# STM32.net
KiCad netlist of a schematic drawn in Altium Designer
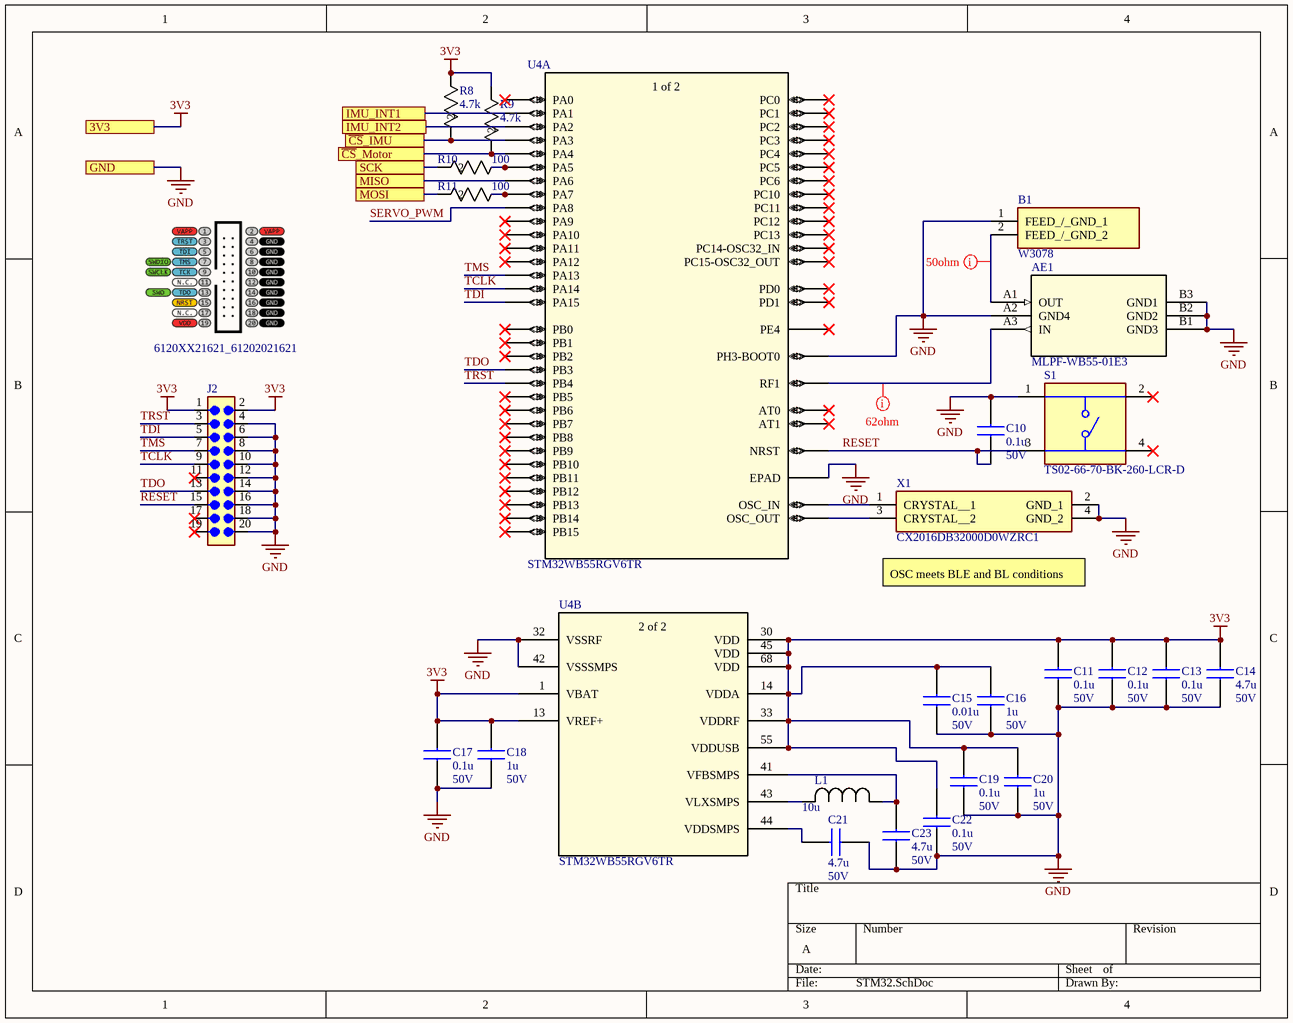
[diagram p0: STM32.SchDoc]

(export (version "E")
  (design (tool "Eeschema 10.0.6"))
  (components
    (comp (ref "AE1")
      (value "MLPF-WB55-01E3")
      (footprint "MLPF-WB55-01E3_STM")
      (description "2.4 GHz Matched filter companion chip for STM32WB55Cx and STM32WB55Rx")
      (fields (field (name "COPYRIGHT") "Copyright (C) 2025 Ultra Librarian. All rights reserved."))
      (libsource (lib "MLPF-WB55-01E3") (part "MLPF-WB55-01E3"))
    )
    (comp (ref "B1")
      (value "W3078")
      (footprint "W3078")
      (description "Antennas CERAMIC W3078 GC380H N")
      (fields (field (name "MOUSER PART NUMBER") "673-W3078"))
      (libsource (lib "W3078") (part "W3078"))
    )
    (comp (ref "C10")
      (value "0.1u")
      (footprint "CAPC2012X145N")
      (description "Multilayer Ceramic Chip Capacitors, Capacitance=0.1u")
      (fields
        (field (name "MANUFACTURER_PART_NUMBER") "KAM21BR71H104JM")
        (field (name "RATED VOLTAGE") "50V")
      )
      (libsource (lib "Caps") (part "KAM21BR71H104JM"))
    )
    (comp (ref "C11")
      (value "0.1u")
      (footprint "CAPC2012X145N")
      (description "Multilayer Ceramic Chip Capacitors, Capacitance=0.1u")
      (fields
        (field (name "MANUFACTURER_PART_NUMBER") "KAM21BR71H104JM")
        (field (name "RATED VOLTAGE") "50V")
      )
      (libsource (lib "Caps") (part "KAM21BR71H104JM"))
    )
    (comp (ref "C12")
      (value "0.1u")
      (footprint "CAPC2012X145N")
      (description "Multilayer Ceramic Chip Capacitors, Capacitance=0.1u")
      (fields
        (field (name "MANUFACTURER_PART_NUMBER") "KAM21BR71H104JM")
        (field (name "RATED VOLTAGE") "50V")
      )
      (libsource (lib "Caps") (part "KAM21BR71H104JM"))
    )
    (comp (ref "C13")
      (value "0.1u")
      (footprint "CAPC2012X145N")
      (description "Multilayer Ceramic Chip Capacitors, Capacitance=0.1u")
      (fields
        (field (name "MANUFACTURER_PART_NUMBER") "KAM21BR71H104JM")
        (field (name "RATED VOLTAGE") "50V")
      )
      (libsource (lib "Caps") (part "KAM21BR71H104JM"))
    )
    (comp (ref "C14")
      (value "4.7u")
      (footprint "CAPC2012X145N")
      (description "Multilayer Ceramic Chip Capacitors, Capacitance=4.7u")
      (fields
        (field (name "MANUFACTURER_PART_NUMBER") "GCM21BR71H474KA55K")
        (field (name "RATED VOLTAGE") "50V")
        (field (name "Comment") "C2012X5R1H475M125AB")
      )
      (libsource (lib "Caps") (part "C2012X5R1H475M125AB"))
    )
    (comp (ref "C15")
      (value "0.01u")
      (footprint "CAPC2012X145N")
      (description "Multilayer Ceramic Chip Capacitors, Capacitance=0.01u")
      (fields
        (field (name "MANUFACTURER_PART_NUMBER") "KAM21BR71H103KT")
        (field (name "RATED VOLTAGE") "50V")
      )
      (libsource (lib "Caps") (part "KAM21BR71H103KT"))
    )
    (comp (ref "C16")
      (value "1u")
      (footprint "CAPC2012X145N")
      (description "Multilayer Ceramic Chip Capacitors, Capacitance=1u")
      (fields
        (field (name "MANUFACTURER_PART_NUMBER") "KGM21AR51H105KU")
        (field (name "RATED VOLTAGE") "50V")
      )
      (libsource (lib "Caps") (part "KGM21AR51H105KU"))
    )
    (comp (ref "C17")
      (value "0.1u")
      (footprint "CAPC2012X145N")
      (description "Multilayer Ceramic Chip Capacitors, Capacitance=0.1u")
      (fields
        (field (name "MANUFACTURER_PART_NUMBER") "KAM21BR71H104JM")
        (field (name "RATED VOLTAGE") "50V")
      )
      (libsource (lib "Caps") (part "KAM21BR71H104JM"))
    )
    (comp (ref "C18")
      (value "1u")
      (footprint "CAPC2012X145N")
      (description "Multilayer Ceramic Chip Capacitors, Capacitance=1u")
      (fields
        (field (name "MANUFACTURER_PART_NUMBER") "KGM21AR51H105KU")
        (field (name "RATED VOLTAGE") "50V")
      )
      (libsource (lib "Caps") (part "KGM21AR51H105KU"))
    )
    (comp (ref "C19")
      (value "0.1u")
      (footprint "CAPC2012X145N")
      (description "Multilayer Ceramic Chip Capacitors, Capacitance=0.1u")
      (fields
        (field (name "MANUFACTURER_PART_NUMBER") "KAM21BR71H104JM")
        (field (name "RATED VOLTAGE") "50V")
      )
      (libsource (lib "Caps") (part "KAM21BR71H104JM"))
    )
    (comp (ref "C20")
      (value "1u")
      (footprint "CAPC2012X145N")
      (description "Multilayer Ceramic Chip Capacitors, Capacitance=1u")
      (fields
        (field (name "MANUFACTURER_PART_NUMBER") "KGM21AR51H105KU")
        (field (name "RATED VOLTAGE") "50V")
      )
      (libsource (lib "Caps") (part "KGM21AR51H105KU"))
    )
    (comp (ref "C21")
      (value "4.7u")
      (footprint "CAPC2012X145N")
      (description "Multilayer Ceramic Chip Capacitors, Capacitance=4.7u")
      (fields
        (field (name "MANUFACTURER_PART_NUMBER") "GCM21BR71H474KA55K")
        (field (name "RATED VOLTAGE") "50V")
        (field (name "Comment") "C2012X5R1H475M125AB")
      )
      (libsource (lib "Caps") (part "C2012X5R1H475M125AB"))
    )
    (comp (ref "C22")
      (value "0.1u")
      (footprint "CAPC2012X145N")
      (description "Multilayer Ceramic Chip Capacitors, Capacitance=0.1u")
      (fields
        (field (name "MANUFACTURER_PART_NUMBER") "KAM21BR71H104JM")
        (field (name "RATED VOLTAGE") "50V")
      )
      (libsource (lib "Caps") (part "KAM21BR71H104JM"))
    )
    (comp (ref "C23")
      (value "4.7u")
      (footprint "CAPC2012X145N")
      (description "Multilayer Ceramic Chip Capacitors, Capacitance=4.7u")
      (fields
        (field (name "MANUFACTURER_PART_NUMBER") "GCM21BR71H474KA55K")
        (field (name "RATED VOLTAGE") "50V")
        (field (name "Comment") "C2012X5R1H475M125AB")
      )
      (libsource (lib "Caps") (part "C2012X5R1H475M125AB"))
    )
    (comp (ref "J2")
      (value "6120XX21621_61202021621")
      (footprint "61202021621")
      (fields
        (field (name "MF") "{'manufacturer': u'~{W}xfcrth Elektronik'}")
        (field (name "MP") "61202021621")
      )
      (libsource (lib "6120XX21621_61202021621") (part "6120XX21621_61202021621"))
    )
    (comp (ref "L1")
      (value "10u")
      (footprint "IND_LQM21FN100M80L_MUR")
      (description "No Description Available")
      (fields
        (field (name "MANUFACTURER_PART_NUMBER") "LQM21FN100M80L")
        (field (name "COPYRIGHT") "Copyright (C) 2025 Ultra Librarian. All rights reserved.")
      )
      (libsource (lib "LQM21FN100M80L") (part "LQM21FN100M80L"))
    )
    (comp (ref "R8")
      (value "4.7k")
      (footprint "RC0805N_YAG")
      (description "RES 0805 4.7k 5% 1/8W")
      (fields (field (name "MANUFACTURER_PART_NUMBER") "RC0805JR-074K7L") (field (name "TOLERANCE") "5%"))
      (libsource (lib "Resistors") (part "RC0805JR-074K7L"))
    )
    (comp (ref "R9")
      (value "4.7k")
      (footprint "RC0805N_YAG")
      (description "RES 0805 4.7k 5% 1/8W")
      (fields (field (name "MANUFACTURER_PART_NUMBER") "RC0805JR-074K7L") (field (name "TOLERANCE") "5%"))
      (libsource (lib "Resistors") (part "RC0805JR-074K7L"))
    )
    (comp (ref "R10")
      (value "100")
      (footprint "RC0805N_YAG")
      (description "RES 0805 100 5% 1/8W")
      (fields (field (name "MANUFACTURER_PART_NUMBER") "RC0805JR-07100RL") (field (name "TOLERANCE") "5%"))
      (libsource (lib "Resistors") (part "RC0805JR-07100RL"))
    )
    (comp (ref "R11")
      (value "100")
      (footprint "RC0805N_YAG")
      (description "RES 0805 100 5% 1/8W")
      (fields (field (name "MANUFACTURER_PART_NUMBER") "RC0805JR-07100RL") (field (name "TOLERANCE") "5%"))
      (libsource (lib "Resistors") (part "RC0805JR-07100RL"))
    )
    (comp (ref "S1")
      (value "TS02-66-70-BK-260-LCR-D")
      (footprint "SW_TS02-66-70-BK-260-LCR-D")
      (description "6 x 6 mm, 7 mm Actuator Height, 260 gf, Black, Long Crimped, Through Hole, SPST, Tactile Switch")
      (fields (field (name "MF") "Same Sky"))
      (libsource (lib "TS02-66-70-BK-260-LCR-D") (part "TS02-66-70-BK-260-LCR-D"))
    )
    (comp (ref "U4")
      (value "STM32WB55RGV6TR")
      (footprint "VFQFN68-8x8mm")
      (fields (field (name "COPYRIGHT") "Copyright (C) 2025 Ultra Librarian. All rights reserved."))
      (libsource (lib "STM32WB55RGV6TR") (part "STM32WB55RGV6TR"))
    )
    (comp (ref "X1")
      (value "CX2016DB32000D0WZRC1")
      (footprint "CX2016DB32000D0WZRC1")
      (description "32 MHz +/-25ppm Crystal 8pF 60 Ohms 4-SMD, No Lead")
      (fields (field (name "MOUSER PART NUMBER") "581-CX2016DB32DWZRC1"))
      (libsource (lib "CX2016DB32000D0WZRC1") (part "CX2016DB32000D0WZRC1"))
    )
  )
  (nets
    (net (code "1") (name "/IMU_INT1") (class "Default")
      (node (ref "U4") (pin "16") (pinfunction "PA1_16") (pintype "bidirectional"))
    )
    (net (code "2") (name "/IMU_INT2") (class "Default")
      (node (ref "U4") (pin "17") (pinfunction "PA2_17") (pintype "bidirectional"))
    )
    (net (code "3") (name "/MISO") (class "Default")
      (node (ref "U4") (pin "21") (pinfunction "PA6_21") (pintype "bidirectional"))
    )
    (net (code "4") (name "/MOSI") (class "Default")
      (node (ref "R11") (pin "2") (pinfunction "2_2") (pintype "passive"))
    )
    (net (code "5") (name "/RESET") (class "Default")
      (node (ref "C10") (pin "1") (pinfunction "1_1") (pintype "passive"))
      (node (ref "J2") (pin "15") (pinfunction "15_15") (pintype "passive"))
      (node (ref "S1") (pin "3") (pinfunction "3_3") (pintype "passive"))
      (node (ref "U4") (pin "8") (pinfunction "NRST_8") (pintype "bidirectional"))
    )
    (net (code "6") (name "/SCK") (class "Default")
      (node (ref "R10") (pin "2") (pinfunction "2_2") (pintype "passive"))
    )
    (net (code "7") (name "/SERVO_PWM") (class "Default")
      (node (ref "U4") (pin "23") (pinfunction "PA8_23") (pintype "bidirectional"))
    )
    (net (code "8") (name "/TCLK") (class "Default")
      (node (ref "J2") (pin "9") (pinfunction "9_9") (pintype "passive"))
      (node (ref "U4") (pin "56") (pinfunction "PA14_56") (pintype "bidirectional"))
    )
    (net (code "9") (name "/TDI") (class "Default")
      (node (ref "J2") (pin "5") (pinfunction "5_5") (pintype "passive"))
      (node (ref "U4") (pin "57") (pinfunction "PA15_57") (pintype "bidirectional"))
    )
    (net (code "10") (name "/TDO") (class "Default")
      (node (ref "J2") (pin "13") (pinfunction "13_13") (pintype "passive"))
      (node (ref "U4") (pin "63") (pinfunction "PB3_63") (pintype "bidirectional"))
    )
    (net (code "11") (name "/TMS") (class "Default")
      (node (ref "J2") (pin "7") (pinfunction "7_7") (pintype "passive"))
      (node (ref "U4") (pin "54") (pinfunction "PA13_54") (pintype "bidirectional"))
    )
    (net (code "12") (name "/TRST") (class "Default")
      (node (ref "J2") (pin "3") (pinfunction "3_3") (pintype "passive"))
      (node (ref "U4") (pin "64") (pinfunction "PB4_64") (pintype "bidirectional"))
    )
    (net (code "13") (name "/~{CS}_IMU") (class "Default")
      (node (ref "R8") (pin "2") (pinfunction "2_2") (pintype "passive"))
      (node (ref "U4") (pin "18") (pinfunction "PA3_18") (pintype "bidirectional"))
    )
    (net (code "14") (name "/~{CS}_Motor") (class "Default")
      (node (ref "R9") (pin "2") (pinfunction "2_2") (pintype "passive"))
      (node (ref "U4") (pin "19") (pinfunction "PA4_19") (pintype "bidirectional"))
    )
    (net (code "15") (name "3V3") (class "Default")
      (node (ref "C11") (pin "2") (pinfunction "2_2") (pintype "passive"))
      (node (ref "C12") (pin "2") (pinfunction "2_2") (pintype "passive"))
      (node (ref "C13") (pin "2") (pinfunction "2_2") (pintype "passive"))
      (node (ref "C14") (pin "2") (pinfunction "2_2") (pintype "passive"))
      (node (ref "C15") (pin "2") (pinfunction "2_2") (pintype "passive"))
      (node (ref "C16") (pin "2") (pinfunction "2_2") (pintype "passive"))
      (node (ref "C17") (pin "2") (pinfunction "2_2") (pintype "passive"))
      (node (ref "C18") (pin "2") (pinfunction "2_2") (pintype "passive"))
      (node (ref "C19") (pin "2") (pinfunction "2_2") (pintype "passive"))
      (node (ref "C20") (pin "2") (pinfunction "2_2") (pintype "passive"))
      (node (ref "C22") (pin "2") (pinfunction "2_2") (pintype "passive"))
      (node (ref "J2") (pin "1") (pinfunction "1_1") (pintype "passive"))
      (node (ref "J2") (pin "2") (pinfunction "2_2") (pintype "passive"))
      (node (ref "R8") (pin "1") (pinfunction "1_1") (pintype "passive"))
      (node (ref "R9") (pin "1") (pinfunction "1_1") (pintype "passive"))
      (node (ref "U4") (pin "1") (pinfunction "VBAT_1") (pintype "power_in"))
      (node (ref "U4") (pin "13") (pinfunction "VREF+_13") (pintype "power_in"))
      (node (ref "U4") (pin "14") (pinfunction "VDDA_14") (pintype "power_in"))
      (node (ref "U4") (pin "30") (pinfunction "VDD_30") (pintype "power_in"))
      (node (ref "U4") (pin "33") (pinfunction "VDDRF_33") (pintype "power_in"))
      (node (ref "U4") (pin "45") (pinfunction "VDD_45") (pintype "power_in"))
      (node (ref "U4") (pin "55") (pinfunction "VDDUSB_55") (pintype "power_in"))
      (node (ref "U4") (pin "68") (pinfunction "VDD_68") (pintype "power_in"))
    )
    (net (code "16") (name "GND") (class "Default")
      (node (ref "AE1") (pin "A2") (pinfunction "GND4_A2") (pintype "power_in"))
      (node (ref "AE1") (pin "B1") (pinfunction "GND3_B1") (pintype "power_in"))
      (node (ref "AE1") (pin "B2") (pinfunction "GND2_B2") (pintype "power_in"))
      (node (ref "AE1") (pin "B3") (pinfunction "GND1_B3") (pintype "power_in"))
      (node (ref "B1") (pin "1") (pinfunction "FEED_/_GND_1_1") (pintype "passive"))
      (node (ref "C10") (pin "2") (pinfunction "2_2") (pintype "passive"))
      (node (ref "C11") (pin "1") (pinfunction "1_1") (pintype "passive"))
      (node (ref "C12") (pin "1") (pinfunction "1_1") (pintype "passive"))
      (node (ref "C13") (pin "1") (pinfunction "1_1") (pintype "passive"))
      (node (ref "C14") (pin "1") (pinfunction "1_1") (pintype "passive"))
      (node (ref "C15") (pin "1") (pinfunction "1_1") (pintype "passive"))
      (node (ref "C16") (pin "1") (pinfunction "1_1") (pintype "passive"))
      (node (ref "C17") (pin "1") (pinfunction "1_1") (pintype "passive"))
      (node (ref "C18") (pin "1") (pinfunction "1_1") (pintype "passive"))
      (node (ref "C19") (pin "1") (pinfunction "1_1") (pintype "passive"))
      (node (ref "C20") (pin "1") (pinfunction "1_1") (pintype "passive"))
      (node (ref "C21") (pin "1") (pinfunction "1_1") (pintype "passive"))
      (node (ref "C22") (pin "1") (pinfunction "1_1") (pintype "passive"))
      (node (ref "C23") (pin "1") (pinfunction "1_1") (pintype "passive"))
      (node (ref "J2") (pin "10") (pinfunction "10_10") (pintype "passive"))
      (node (ref "J2") (pin "12") (pinfunction "12_12") (pintype "passive"))
      (node (ref "J2") (pin "14") (pinfunction "14_14") (pintype "passive"))
      (node (ref "J2") (pin "16") (pinfunction "16_16") (pintype "passive"))
      (node (ref "J2") (pin "18") (pinfunction "18_18") (pintype "passive"))
      (node (ref "J2") (pin "20") (pinfunction "20_20") (pintype "passive"))
      (node (ref "J2") (pin "4") (pinfunction "4_4") (pintype "passive"))
      (node (ref "J2") (pin "6") (pinfunction "6_6") (pintype "passive"))
      (node (ref "J2") (pin "8") (pinfunction "8_8") (pintype "passive"))
      (node (ref "S1") (pin "1") (pinfunction "1_1") (pintype "passive"))
      (node (ref "U4") (pin "32") (pinfunction "VSSRF_32") (pintype "power_in"))
      (node (ref "U4") (pin "42") (pinfunction "VSSSMPS_42") (pintype "power_in"))
      (node (ref "U4") (pin "5") (pinfunction "PH3-BOOT0_5") (pintype "bidirectional"))
      (node (ref "U4") (pin "69") (pinfunction "EPAD_69") (pintype "passive"))
      (node (ref "X1") (pin "2") (pinfunction "GND_1_2") (pintype "passive"))
      (node (ref "X1") (pin "4") (pinfunction "GND_2_4") (pintype "passive"))
    )
    (net (code "17") (name "Net-(AE1-IN)") (class "Default")
      (node (ref "AE1") (pin "A3") (pinfunction "IN_A3") (pintype "output"))
      (node (ref "U4") (pin "31") (pinfunction "RF1_31") (pintype "bidirectional"))
    )
    (net (code "18") (name "Net-(AE1-OUT)") (class "Default")
      (node (ref "AE1") (pin "A1") (pinfunction "OUT_A1") (pintype "input"))
      (node (ref "B1") (pin "2") (pinfunction "FEED_/_GND_2_2") (pintype "passive"))
    )
    (net (code "19") (name "Net-(U4A-OSC_IN)") (class "Default")
      (node (ref "U4") (pin "35") (pinfunction "OSC_IN_35") (pintype "bidirectional"))
      (node (ref "X1") (pin "1") (pinfunction "CRYSTAL__1_1") (pintype "passive"))
    )
    (net (code "20") (name "Net-(U4A-OSC_OUT)") (class "Default")
      (node (ref "U4") (pin "34") (pinfunction "OSC_OUT_34") (pintype "bidirectional"))
      (node (ref "X1") (pin "3") (pinfunction "CRYSTAL__2_3") (pintype "passive"))
    )
    (net (code "21") (name "Net-(U4A-PA5)") (class "Default")
      (node (ref "R10") (pin "1") (pinfunction "1_1") (pintype "passive"))
      (node (ref "U4") (pin "20") (pinfunction "PA5_20") (pintype "bidirectional"))
    )
    (net (code "22") (name "Net-(U4A-PA7)") (class "Default")
      (node (ref "R11") (pin "1") (pinfunction "1_1") (pintype "passive"))
      (node (ref "U4") (pin "22") (pinfunction "PA7_22") (pintype "bidirectional"))
    )
    (net (code "23") (name "Net-(U4B-VDDSMPS)") (class "Default")
      (node (ref "C21") (pin "2") (pinfunction "2_2") (pintype "passive"))
      (node (ref "U4") (pin "44") (pinfunction "VDDSMPS_44") (pintype "power_in"))
    )
    (net (code "24") (name "Net-(U4B-VFBSMPS)") (class "Default")
      (node (ref "C23") (pin "2") (pinfunction "2_2") (pintype "passive"))
      (node (ref "L1") (pin "1") (pinfunction "1_1") (pintype "passive"))
      (node (ref "U4") (pin "41") (pinfunction "VFBSMPS_41") (pintype "power_in"))
    )
    (net (code "25") (name "Net-(U4B-VLXSMPS)") (class "Default")
      (node (ref "L1") (pin "2") (pinfunction "2_2") (pintype "passive"))
      (node (ref "U4") (pin "43") (pinfunction "VLXSMPS_43") (pintype "power_in"))
    )
    (net (code "26") (name "unconnected-(J2-Pad11)") (class "Default")
      (node (ref "J2") (pin "11") (pinfunction "11_11") (pintype "passive+no_connect"))
    )
    (net (code "27") (name "unconnected-(J2-Pad17)") (class "Default")
      (node (ref "J2") (pin "17") (pinfunction "17_17") (pintype "passive+no_connect"))
    )
    (net (code "28") (name "unconnected-(J2-Pad19)") (class "Default")
      (node (ref "J2") (pin "19") (pinfunction "19_19") (pintype "passive+no_connect"))
    )
    (net (code "29") (name "unconnected-(S1-Pad2)") (class "Default")
      (node (ref "S1") (pin "2") (pinfunction "2_2") (pintype "passive+no_connect"))
    )
    (net (code "30") (name "unconnected-(S1-Pad4)") (class "Default")
      (node (ref "S1") (pin "4") (pinfunction "4_4") (pintype "passive+no_connect"))
    )
    (net (code "31") (name "unconnected-(U4A-AT0-Pad36)") (class "Default")
      (node (ref "U4") (pin "36") (pinfunction "AT0_36") (pintype "bidirectional+no_connect"))
    )
    (net (code "32") (name "unconnected-(U4A-AT1-Pad37)") (class "Default")
      (node (ref "U4") (pin "37") (pinfunction "AT1_37") (pintype "bidirectional+no_connect"))
    )
    (net (code "33") (name "unconnected-(U4A-PA0-Pad15)") (class "Default")
      (node (ref "U4") (pin "15") (pinfunction "PA0_15") (pintype "bidirectional+no_connect"))
    )
    (net (code "34") (name "unconnected-(U4A-PA9-Pad24)") (class "Default")
      (node (ref "U4") (pin "24") (pinfunction "PA9_24") (pintype "bidirectional+no_connect"))
    )
    (net (code "35") (name "unconnected-(U4A-PA10-Pad51)") (class "Default")
      (node (ref "U4") (pin "51") (pinfunction "PA10_51") (pintype "bidirectional+no_connect"))
    )
    (net (code "36") (name "unconnected-(U4A-PA11-Pad52)") (class "Default")
      (node (ref "U4") (pin "52") (pinfunction "PA11_52") (pintype "bidirectional+no_connect"))
    )
    (net (code "37") (name "unconnected-(U4A-PA12-Pad53)") (class "Default")
      (node (ref "U4") (pin "53") (pinfunction "PA12_53") (pintype "bidirectional+no_connect"))
    )
    (net (code "38") (name "unconnected-(U4A-PB0-Pad38)") (class "Default")
      (node (ref "U4") (pin "38") (pinfunction "PB0_38") (pintype "bidirectional+no_connect"))
    )
    (net (code "39") (name "unconnected-(U4A-PB1-Pad39)") (class "Default")
      (node (ref "U4") (pin "39") (pinfunction "PB1_39") (pintype "bidirectional+no_connect"))
    )
    (net (code "40") (name "unconnected-(U4A-PB2-Pad27)") (class "Default")
      (node (ref "U4") (pin "27") (pinfunction "PB2_27") (pintype "bidirectional+no_connect"))
    )
    (net (code "41") (name "unconnected-(U4A-PB5-Pad65)") (class "Default")
      (node (ref "U4") (pin "65") (pinfunction "PB5_65") (pintype "bidirectional+no_connect"))
    )
    (net (code "42") (name "unconnected-(U4A-PB6-Pad66)") (class "Default")
      (node (ref "U4") (pin "66") (pinfunction "PB6_66") (pintype "bidirectional+no_connect"))
    )
    (net (code "43") (name "unconnected-(U4A-PB7-Pad67)") (class "Default")
      (node (ref "U4") (pin "67") (pinfunction "PB7_67") (pintype "bidirectional+no_connect"))
    )
    (net (code "44") (name "unconnected-(U4A-PB8-Pad6)") (class "Default")
      (node (ref "U4") (pin "6") (pinfunction "PB8_6") (pintype "bidirectional+no_connect"))
    )
    (net (code "45") (name "unconnected-(U4A-PB9-Pad7)") (class "Default")
      (node (ref "U4") (pin "7") (pinfunction "PB9_7") (pintype "bidirectional+no_connect"))
    )
    (net (code "46") (name "unconnected-(U4A-PB10-Pad28)") (class "Default")
      (node (ref "U4") (pin "28") (pinfunction "PB10_28") (pintype "bidirectional+no_connect"))
    )
    (net (code "47") (name "unconnected-(U4A-PB11-Pad29)") (class "Default")
      (node (ref "U4") (pin "29") (pinfunction "PB11_29") (pintype "bidirectional+no_connect"))
    )
    (net (code "48") (name "unconnected-(U4A-PB12-Pad46)") (class "Default")
      (node (ref "U4") (pin "46") (pinfunction "PB12_46") (pintype "bidirectional+no_connect"))
    )
    (net (code "49") (name "unconnected-(U4A-PB13-Pad47)") (class "Default")
      (node (ref "U4") (pin "47") (pinfunction "PB13_47") (pintype "bidirectional+no_connect"))
    )
    (net (code "50") (name "unconnected-(U4A-PB14-Pad48)") (class "Default")
      (node (ref "U4") (pin "48") (pinfunction "PB14_48") (pintype "bidirectional+no_connect"))
    )
    (net (code "51") (name "unconnected-(U4A-PB15-Pad49)") (class "Default")
      (node (ref "U4") (pin "49") (pinfunction "PB15_49") (pintype "bidirectional+no_connect"))
    )
    (net (code "52") (name "unconnected-(U4A-PC0-Pad9)") (class "Default")
      (node (ref "U4") (pin "9") (pinfunction "PC0_9") (pintype "bidirectional+no_connect"))
    )
    (net (code "53") (name "unconnected-(U4A-PC1-Pad10)") (class "Default")
      (node (ref "U4") (pin "10") (pinfunction "PC1_10") (pintype "bidirectional+no_connect"))
    )
    (net (code "54") (name "unconnected-(U4A-PC2-Pad11)") (class "Default")
      (node (ref "U4") (pin "11") (pinfunction "PC2_11") (pintype "bidirectional+no_connect"))
    )
    (net (code "55") (name "unconnected-(U4A-PC3-Pad12)") (class "Default")
      (node (ref "U4") (pin "12") (pinfunction "PC3_12") (pintype "bidirectional+no_connect"))
    )
    (net (code "56") (name "unconnected-(U4A-PC4-Pad25)") (class "Default")
      (node (ref "U4") (pin "25") (pinfunction "PC4_25") (pintype "bidirectional+no_connect"))
    )
    (net (code "57") (name "unconnected-(U4A-PC5-Pad26)") (class "Default")
      (node (ref "U4") (pin "26") (pinfunction "PC5_26") (pintype "bidirectional+no_connect"))
    )
    (net (code "58") (name "unconnected-(U4A-PC6-Pad50)") (class "Default")
      (node (ref "U4") (pin "50") (pinfunction "PC6_50") (pintype "bidirectional+no_connect"))
    )
    (net (code "59") (name "unconnected-(U4A-PC10-Pad58)") (class "Default")
      (node (ref "U4") (pin "58") (pinfunction "PC10_58") (pintype "bidirectional+no_connect"))
    )
    (net (code "60") (name "unconnected-(U4A-PC11-Pad59)") (class "Default")
      (node (ref "U4") (pin "59") (pinfunction "PC11_59") (pintype "bidirectional+no_connect"))
    )
    (net (code "61") (name "unconnected-(U4A-PC12-Pad60)") (class "Default")
      (node (ref "U4") (pin "60") (pinfunction "PC12_60") (pintype "bidirectional+no_connect"))
    )
    (net (code "62") (name "unconnected-(U4A-PC13-Pad2)") (class "Default")
      (node (ref "U4") (pin "2") (pinfunction "PC13_2") (pintype "bidirectional+no_connect"))
    )
    (net (code "63") (name "unconnected-(U4A-PC14-OSC32_IN-Pad3)") (class "Default")
      (node (ref "U4") (pin "3") (pinfunction "PC14-OSC32_IN_3") (pintype "bidirectional+no_connect"))
    )
    (net (code "64") (name "unconnected-(U4A-PC15-OSC32_OUT-Pad4)") (class "Default")
      (node (ref "U4") (pin "4") (pinfunction "PC15-OSC32_OUT_4") (pintype "bidirectional+no_connect"))
    )
    (net (code "65") (name "unconnected-(U4A-PD0-Pad61)") (class "Default")
      (node (ref "U4") (pin "61") (pinfunction "PD0_61") (pintype "bidirectional+no_connect"))
    )
    (net (code "66") (name "unconnected-(U4A-PD1-Pad62)") (class "Default")
      (node (ref "U4") (pin "62") (pinfunction "PD1_62") (pintype "bidirectional+no_connect"))
    )
    (net (code "67") (name "unconnected-(U4A-PE4-Pad40)") (class "Default")
      (node (ref "U4") (pin "40") (pinfunction "PE4_40") (pintype "power_in+no_connect"))
    )
  )
)
